# ESP32_RelayControl.net
KiCad netlist of a schematic drawn in EasyEDA
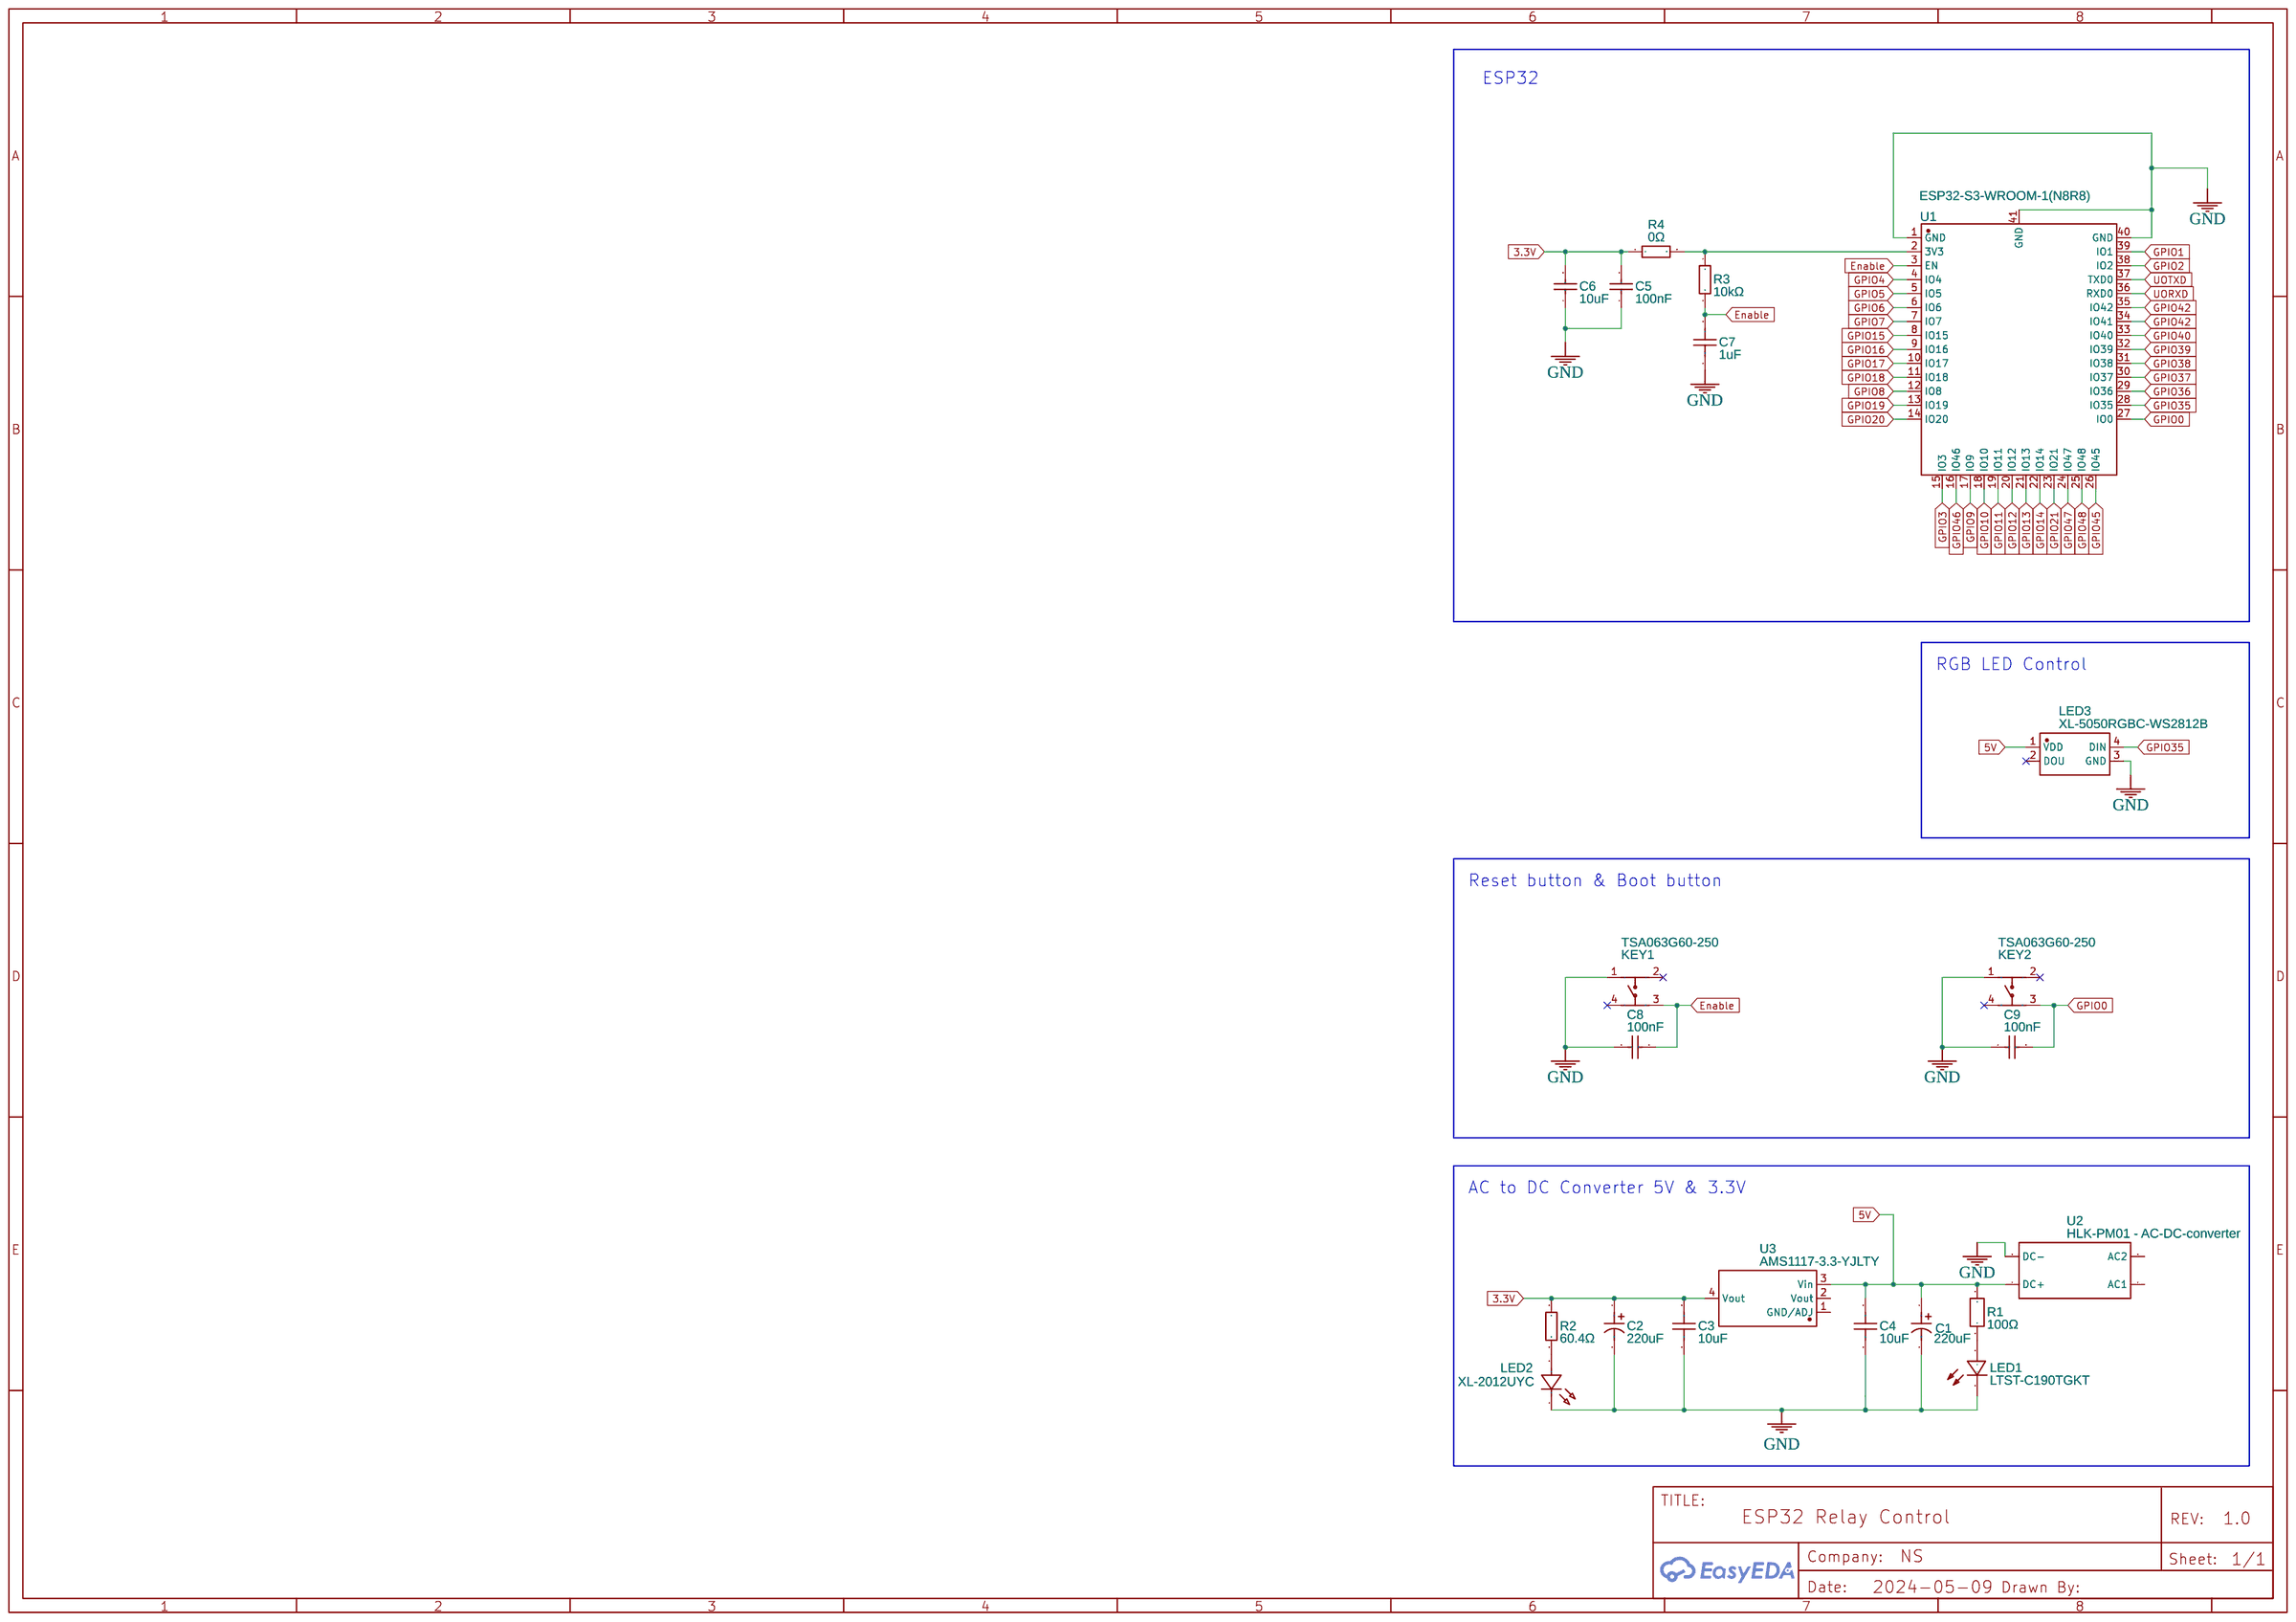
[diagram p0: schematic sheet]

(export (version "E")
  (design (tool "Eeschema 10.0.6"))
  (components
    (comp (ref "C1")
      (value "220uF")
      (fields
        (field (name "Manufacturer Part") "MVG 16V 220UF 6.3*7.7")
        (field (name "Manufacturer") "SAMYOUNG(韩国三莹)")
      )
      (libsource (lib "") (part "MVG 16V 220UF 6.3*7.7"))
    )
    (comp (ref "C2")
      (value "220uF")
      (fields
        (field (name "Manufacturer Part") "MVG 16V 220UF 6.3*7.7")
        (field (name "Manufacturer") "SAMYOUNG(韩国三莹)")
      )
      (libsource (lib "") (part "MVG 16V 220UF 6.3*7.7"))
    )
    (comp (ref "C3")
      (value "10uF")
      (fields (field (name "Manufacturer Part") "0805F106M160NT") (field (name "Manufacturer") "FH(风华)"))
      (libsource (lib "") (part "0805F106M160NT"))
    )
    (comp (ref "C4")
      (value "10uF")
      (fields (field (name "Manufacturer Part") "0805F106M160NT") (field (name "Manufacturer") "FH(风华)"))
      (libsource (lib "") (part "0805F106M160NT"))
    )
    (comp (ref "C5")
      (value "100nF")
      (fields (field (name "Manufacturer Part") "0805B104K500NT") (field (name "Manufacturer") "FH(风华)"))
      (libsource (lib "") (part "0805B104K500NT_1"))
    )
    (comp (ref "C6")
      (value "10uF")
      (fields (field (name "Manufacturer Part") "0805X106K250NT") (field (name "Manufacturer") "FH(风华)"))
      (libsource (lib "") (part "0805X106K250NT"))
    )
    (comp (ref "C7")
      (value "1uF")
      (fields (field (name "Manufacturer Part") "0805B105K160NT") (field (name "Manufacturer") "FH(风华)"))
      (libsource (lib "") (part "0805B105K160NT"))
    )
    (comp (ref "C8")
      (value "100nF")
      (fields (field (name "Manufacturer Part") "0805B104K500NT") (field (name "Manufacturer") "FH(风华)"))
      (libsource (lib "") (part "0805B104K500NT"))
    )
    (comp (ref "C9")
      (value "100nF")
      (fields (field (name "Manufacturer Part") "0805B104K500NT") (field (name "Manufacturer") "FH(风华)"))
      (libsource (lib "") (part "0805B104K500NT"))
    )
    (comp (ref "KEY1")
      (value "TSA063G60-250")
      (fields (field (name "Manufacturer") "BRIGHT(博瑞泰)"))
      (libsource (lib "") (part "TSA063G60-250"))
    )
    (comp (ref "KEY2")
      (value "TSA063G60-250")
      (fields (field (name "Manufacturer") "BRIGHT(博瑞泰)"))
      (libsource (lib "") (part "TSA063G60-250"))
    )
    (comp (ref "LED1")
      (value "LTST-C190TGKT")
      (fields (field (name "Manufacturer") "LITEON(光宝)"))
      (libsource (lib "") (part "LTST-C190TGKT"))
    )
    (comp (ref "LED2")
      (value "XL-2012UYC")
      (fields (field (name "Manufacturer") "XINGLIGHT(成兴光)"))
      (libsource (lib "") (part "XL-2012UYC"))
    )
    (comp (ref "LED3")
      (value "XL-5050RGBC-WS2812B")
      (fields (field (name "Manufacturer") "XINGLIGHT(成兴光)"))
      (libsource (lib "") (part "XL-5050RGBC-WS2812B"))
    )
    (comp (ref "R1")
      (value "100Ω")
      (fields
        (field (name "Manufacturer Part") "CRCW0805100RFKEA")
        (field (name "Manufacturer") "VISHAY(威世)")
      )
      (libsource (lib "") (part "CRCW0805100RFKEA"))
    )
    (comp (ref "R2")
      (value "60.4Ω")
      (fields (field (name "Manufacturer Part") "RC0805FR-0760R4L") (field (name "Manufacturer") "YAGEO(国巨)"))
      (libsource (lib "") (part "RC0805FR-0760R4L"))
    )
    (comp (ref "R3")
      (value "10kΩ")
      (fields (field (name "Manufacturer Part") "AF0805JR-0710KL") (field (name "Manufacturer") "YAGEO(国巨)"))
      (libsource (lib "") (part "AF0805JR-0710KL"))
    )
    (comp (ref "R4")
      (value "0Ω")
      (fields
        (field (name "Manufacturer Part") "0805W8F0000T5E")
        (field (name "Manufacturer") "UNI-ROYAL(厚声)")
      )
      (libsource (lib "") (part "0805W8F0000T5E"))
    )
    (comp (ref "U1")
      (value "ESP32-S3-WROOM-1(N8R8)")
      (fields
        (field (name "Manufacturer Part") "ESP32-S3-WROOM-1-N8R8")
        (field (name "Manufacturer") "ESPRESSIF(乐鑫)")
      )
      (libsource (lib "") (part "ESP32-S3-WROOM-1(N8R8)"))
    )
    (comp (ref "U2")
      (value "HLK-PM01 - AC-DC-converter")
      (fields (field (name "Manufacturer Part") "HLK-PM01") (field (name "Manufacturer") "HI-LINK(海凌科)"))
      (libsource (lib "") (part "HLK-PM01 - AC-DC-converter"))
    )
    (comp (ref "U3") (value "AMS1117-3.3-YJLTY") (libsource (lib "") (part "AMS1117-3.3-YJLTY")))
  )
  (nets
    (net (code "1") (name "3.3V") (class "Default")
      (node (ref "C2") (pin "1") (pinfunction "1_1") (pintype "input"))
      (node (ref "C3") (pin "2") (pinfunction "2_2") (pintype "unspecified"))
      (node (ref "C5") (pin "2") (pinfunction "2_2") (pintype "input"))
      (node (ref "C6") (pin "2") (pinfunction "2_2") (pintype "input"))
      (node (ref "R2") (pin "2") (pinfunction "2_2") (pintype "unspecified"))
      (node (ref "R4") (pin "1") (pinfunction "1_1") (pintype "input"))
      (node (ref "U3") (pin "4") (pinfunction "Vout_4") (pintype "unspecified"))
    )
    (net (code "2") (name "5V") (class "Default")
      (node (ref "C1") (pin "1") (pinfunction "1_1") (pintype "input"))
      (node (ref "C4") (pin "2") (pinfunction "2_2") (pintype "unspecified"))
      (node (ref "LED3") (pin "1") (pinfunction "VDD_1") (pintype "unspecified"))
      (node (ref "R1") (pin "2") (pinfunction "2_2") (pintype "unspecified"))
      (node (ref "U2") (pin "4") (pinfunction "DC+_4") (pintype "unspecified"))
      (node (ref "U3") (pin "3") (pinfunction "Vin_3") (pintype "unspecified"))
    )
    (net (code "3") (name "Enable") (class "Default")
      (node (ref "C7") (pin "2") (pinfunction "2_2") (pintype "unspecified"))
      (node (ref "C8") (pin "2") (pinfunction "2_2") (pintype "input"))
      (node (ref "KEY1") (pin "3") (pinfunction "3_3") (pintype "unspecified"))
      (node (ref "R3") (pin "2") (pinfunction "2_2") (pintype "input"))
      (node (ref "U1") (pin "3") (pinfunction "EN_3") (pintype "unspecified"))
    )
    (net (code "4") (name "GND") (class "Default")
      (node (ref "C1") (pin "2") (pinfunction "2_2") (pintype "input"))
      (node (ref "C2") (pin "2") (pinfunction "2_2") (pintype "input"))
      (node (ref "C3") (pin "1") (pinfunction "1_1") (pintype "unspecified"))
      (node (ref "C4") (pin "1") (pinfunction "1_1") (pintype "unspecified"))
      (node (ref "C5") (pin "1") (pinfunction "1_1") (pintype "input"))
      (node (ref "C6") (pin "1") (pinfunction "1_1") (pintype "input"))
      (node (ref "C7") (pin "1") (pinfunction "1_1") (pintype "unspecified"))
      (node (ref "C8") (pin "1") (pinfunction "1_1") (pintype "input"))
      (node (ref "C9") (pin "1") (pinfunction "1_1") (pintype "input"))
      (node (ref "KEY1") (pin "1") (pinfunction "1_1") (pintype "unspecified"))
      (node (ref "KEY2") (pin "1") (pinfunction "1_1") (pintype "unspecified"))
      (node (ref "LED1") (pin "1") (pinfunction "-_1") (pintype "unspecified"))
      (node (ref "LED2") (pin "1") (pinfunction "K_1") (pintype "unspecified"))
      (node (ref "LED3") (pin "3") (pinfunction "GND_3") (pintype "unspecified"))
      (node (ref "U1") (pin "1") (pinfunction "GND_1") (pintype "unspecified"))
      (node (ref "U1") (pin "40") (pinfunction "GND_40") (pintype "unspecified"))
      (node (ref "U1") (pin "41") (pinfunction "GND_41") (pintype "unspecified"))
      (node (ref "U2") (pin "3") (pinfunction "DC-_3") (pintype "unspecified"))
    )
    (net (code "5") (name "GPIO0") (class "Default")
      (node (ref "C9") (pin "2") (pinfunction "2_2") (pintype "input"))
      (node (ref "KEY2") (pin "3") (pinfunction "3_3") (pintype "unspecified"))
      (node (ref "U1") (pin "27") (pinfunction "IO0_27") (pintype "unspecified"))
    )
    (net (code "6") (name "GPIO1") (class "Default")
      (node (ref "U1") (pin "39") (pinfunction "IO1_39") (pintype "unspecified"))
    )
    (net (code "7") (name "GPIO2") (class "Default")
      (node (ref "U1") (pin "38") (pinfunction "IO2_38") (pintype "unspecified"))
    )
    (net (code "8") (name "GPIO3") (class "Default")
      (node (ref "U1") (pin "15") (pinfunction "IO3_15") (pintype "unspecified"))
    )
    (net (code "9") (name "GPIO4") (class "Default")
      (node (ref "U1") (pin "4") (pinfunction "IO4_4") (pintype "unspecified"))
    )
    (net (code "10") (name "GPIO5") (class "Default")
      (node (ref "U1") (pin "5") (pinfunction "IO5_5") (pintype "unspecified"))
    )
    (net (code "11") (name "GPIO6") (class "Default")
      (node (ref "U1") (pin "6") (pinfunction "IO6_6") (pintype "unspecified"))
    )
    (net (code "12") (name "GPIO7") (class "Default")
      (node (ref "U1") (pin "7") (pinfunction "IO7_7") (pintype "unspecified"))
    )
    (net (code "13") (name "GPIO8") (class "Default")
      (node (ref "U1") (pin "12") (pinfunction "IO8_12") (pintype "unspecified"))
    )
    (net (code "14") (name "GPIO9") (class "Default")
      (node (ref "U1") (pin "17") (pinfunction "IO9_17") (pintype "unspecified"))
    )
    (net (code "15") (name "GPIO10") (class "Default")
      (node (ref "U1") (pin "18") (pinfunction "IO10_18") (pintype "unspecified"))
    )
    (net (code "16") (name "GPIO11") (class "Default")
      (node (ref "U1") (pin "19") (pinfunction "IO11_19") (pintype "unspecified"))
    )
    (net (code "17") (name "GPIO12") (class "Default")
      (node (ref "U1") (pin "20") (pinfunction "IO12_20") (pintype "unspecified"))
    )
    (net (code "18") (name "GPIO13") (class "Default")
      (node (ref "U1") (pin "21") (pinfunction "IO13_21") (pintype "unspecified"))
    )
    (net (code "19") (name "GPIO14") (class "Default")
      (node (ref "U1") (pin "22") (pinfunction "IO14_22") (pintype "unspecified"))
    )
    (net (code "20") (name "GPIO15") (class "Default")
      (node (ref "U1") (pin "8") (pinfunction "IO15_8") (pintype "unspecified"))
    )
    (net (code "21") (name "GPIO16") (class "Default")
      (node (ref "U1") (pin "9") (pinfunction "IO16_9") (pintype "unspecified"))
    )
    (net (code "22") (name "GPIO17") (class "Default")
      (node (ref "U1") (pin "10") (pinfunction "IO17_10") (pintype "unspecified"))
    )
    (net (code "23") (name "GPIO18") (class "Default")
      (node (ref "U1") (pin "11") (pinfunction "IO18_11") (pintype "unspecified"))
    )
    (net (code "24") (name "GPIO19") (class "Default")
      (node (ref "U1") (pin "13") (pinfunction "IO19_13") (pintype "unspecified"))
    )
    (net (code "25") (name "GPIO20") (class "Default")
      (node (ref "U1") (pin "14") (pinfunction "IO20_14") (pintype "unspecified"))
    )
    (net (code "26") (name "GPIO21") (class "Default")
      (node (ref "U1") (pin "23") (pinfunction "IO21_23") (pintype "unspecified"))
    )
    (net (code "27") (name "GPIO35") (class "Default")
      (node (ref "LED3") (pin "4") (pinfunction "DIN_4") (pintype "unspecified"))
      (node (ref "U1") (pin "28") (pinfunction "IO35_28") (pintype "unspecified"))
    )
    (net (code "28") (name "GPIO36") (class "Default")
      (node (ref "U1") (pin "29") (pinfunction "IO36_29") (pintype "unspecified"))
    )
    (net (code "29") (name "GPIO37") (class "Default")
      (node (ref "U1") (pin "30") (pinfunction "IO37_30") (pintype "unspecified"))
    )
    (net (code "30") (name "GPIO38") (class "Default")
      (node (ref "U1") (pin "31") (pinfunction "IO38_31") (pintype "unspecified"))
    )
    (net (code "31") (name "GPIO39") (class "Default")
      (node (ref "U1") (pin "32") (pinfunction "IO39_32") (pintype "unspecified"))
    )
    (net (code "32") (name "GPIO40") (class "Default")
      (node (ref "U1") (pin "33") (pinfunction "IO40_33") (pintype "unspecified"))
    )
    (net (code "33") (name "GPIO42") (class "Default")
      (node (ref "U1") (pin "34") (pinfunction "IO41_34") (pintype "unspecified"))
      (node (ref "U1") (pin "35") (pinfunction "IO42_35") (pintype "unspecified"))
    )
    (net (code "34") (name "GPIO45") (class "Default")
      (node (ref "U1") (pin "26") (pinfunction "IO45_26") (pintype "unspecified"))
    )
    (net (code "35") (name "GPIO46") (class "Default")
      (node (ref "U1") (pin "16") (pinfunction "IO46_16") (pintype "unspecified"))
    )
    (net (code "36") (name "GPIO47") (class "Default")
      (node (ref "U1") (pin "24") (pinfunction "IO47_24") (pintype "unspecified"))
    )
    (net (code "37") (name "GPIO48") (class "Default")
      (node (ref "U1") (pin "25") (pinfunction "IO48_25") (pintype "unspecified"))
    )
    (net (code "38") (name "Net-(LED1-+)") (class "Default")
      (node (ref "LED1") (pin "2") (pinfunction "+_2") (pintype "unspecified"))
      (node (ref "R1") (pin "1") (pinfunction "1_1") (pintype "unspecified"))
    )
    (net (code "39") (name "Net-(LED2-A)") (class "Default")
      (node (ref "LED2") (pin "2") (pinfunction "A_2") (pintype "unspecified"))
      (node (ref "R2") (pin "1") (pinfunction "1_1") (pintype "unspecified"))
    )
    (net (code "40") (name "Net-(U1-3V3)") (class "Default")
      (node (ref "R3") (pin "1") (pinfunction "1_1") (pintype "input"))
      (node (ref "R4") (pin "2") (pinfunction "2_2") (pintype "input"))
      (node (ref "U1") (pin "2") (pinfunction "3V3_2") (pintype "unspecified"))
    )
    (net (code "41") (name "UORXD") (class "Default")
      (node (ref "U1") (pin "36") (pinfunction "RXD0_36") (pintype "unspecified"))
    )
    (net (code "42") (name "UOTXD") (class "Default")
      (node (ref "U1") (pin "37") (pinfunction "TXD0_37") (pintype "unspecified"))
    )
    (net (code "43") (name "unconnected-(KEY1-Pad2)") (class "Default")
      (node (ref "KEY1") (pin "2") (pinfunction "2_2") (pintype "unspecified+no_connect"))
    )
    (net (code "44") (name "unconnected-(KEY1-Pad4)") (class "Default")
      (node (ref "KEY1") (pin "4") (pinfunction "4_4") (pintype "unspecified+no_connect"))
    )
    (net (code "45") (name "unconnected-(KEY2-Pad2)") (class "Default")
      (node (ref "KEY2") (pin "2") (pinfunction "2_2") (pintype "unspecified+no_connect"))
    )
    (net (code "46") (name "unconnected-(KEY2-Pad4)") (class "Default")
      (node (ref "KEY2") (pin "4") (pinfunction "4_4") (pintype "unspecified+no_connect"))
    )
    (net (code "47") (name "unconnected-(LED3-DOU-Pad2)") (class "Default")
      (node (ref "LED3") (pin "2") (pinfunction "DOU_2") (pintype "unspecified+no_connect"))
    )
    (net (code "48") (name "unconnected-(U2-AC1-Pad1)") (class "Default")
      (node (ref "U2") (pin "1") (pinfunction "AC1_1") (pintype "input"))
    )
    (net (code "49") (name "unconnected-(U2-AC2-Pad2)") (class "Default")
      (node (ref "U2") (pin "2") (pinfunction "AC2_2") (pintype "input"))
    )
    (net (code "50") (name "unconnected-(U3-GND{slash}ADJ-Pad1)") (class "Default")
      (node (ref "U3") (pin "1") (pinfunction "GND/ADJ_1") (pintype "unspecified"))
    )
    (net (code "51") (name "unconnected-(U3-Vout-Pad2)") (class "Default")
      (node (ref "U3") (pin "2") (pinfunction "Vout_2") (pintype "unspecified"))
    )
  )
)
